# PWR_PROT.net
KiCad netlist of a schematic drawn in Altium Designer
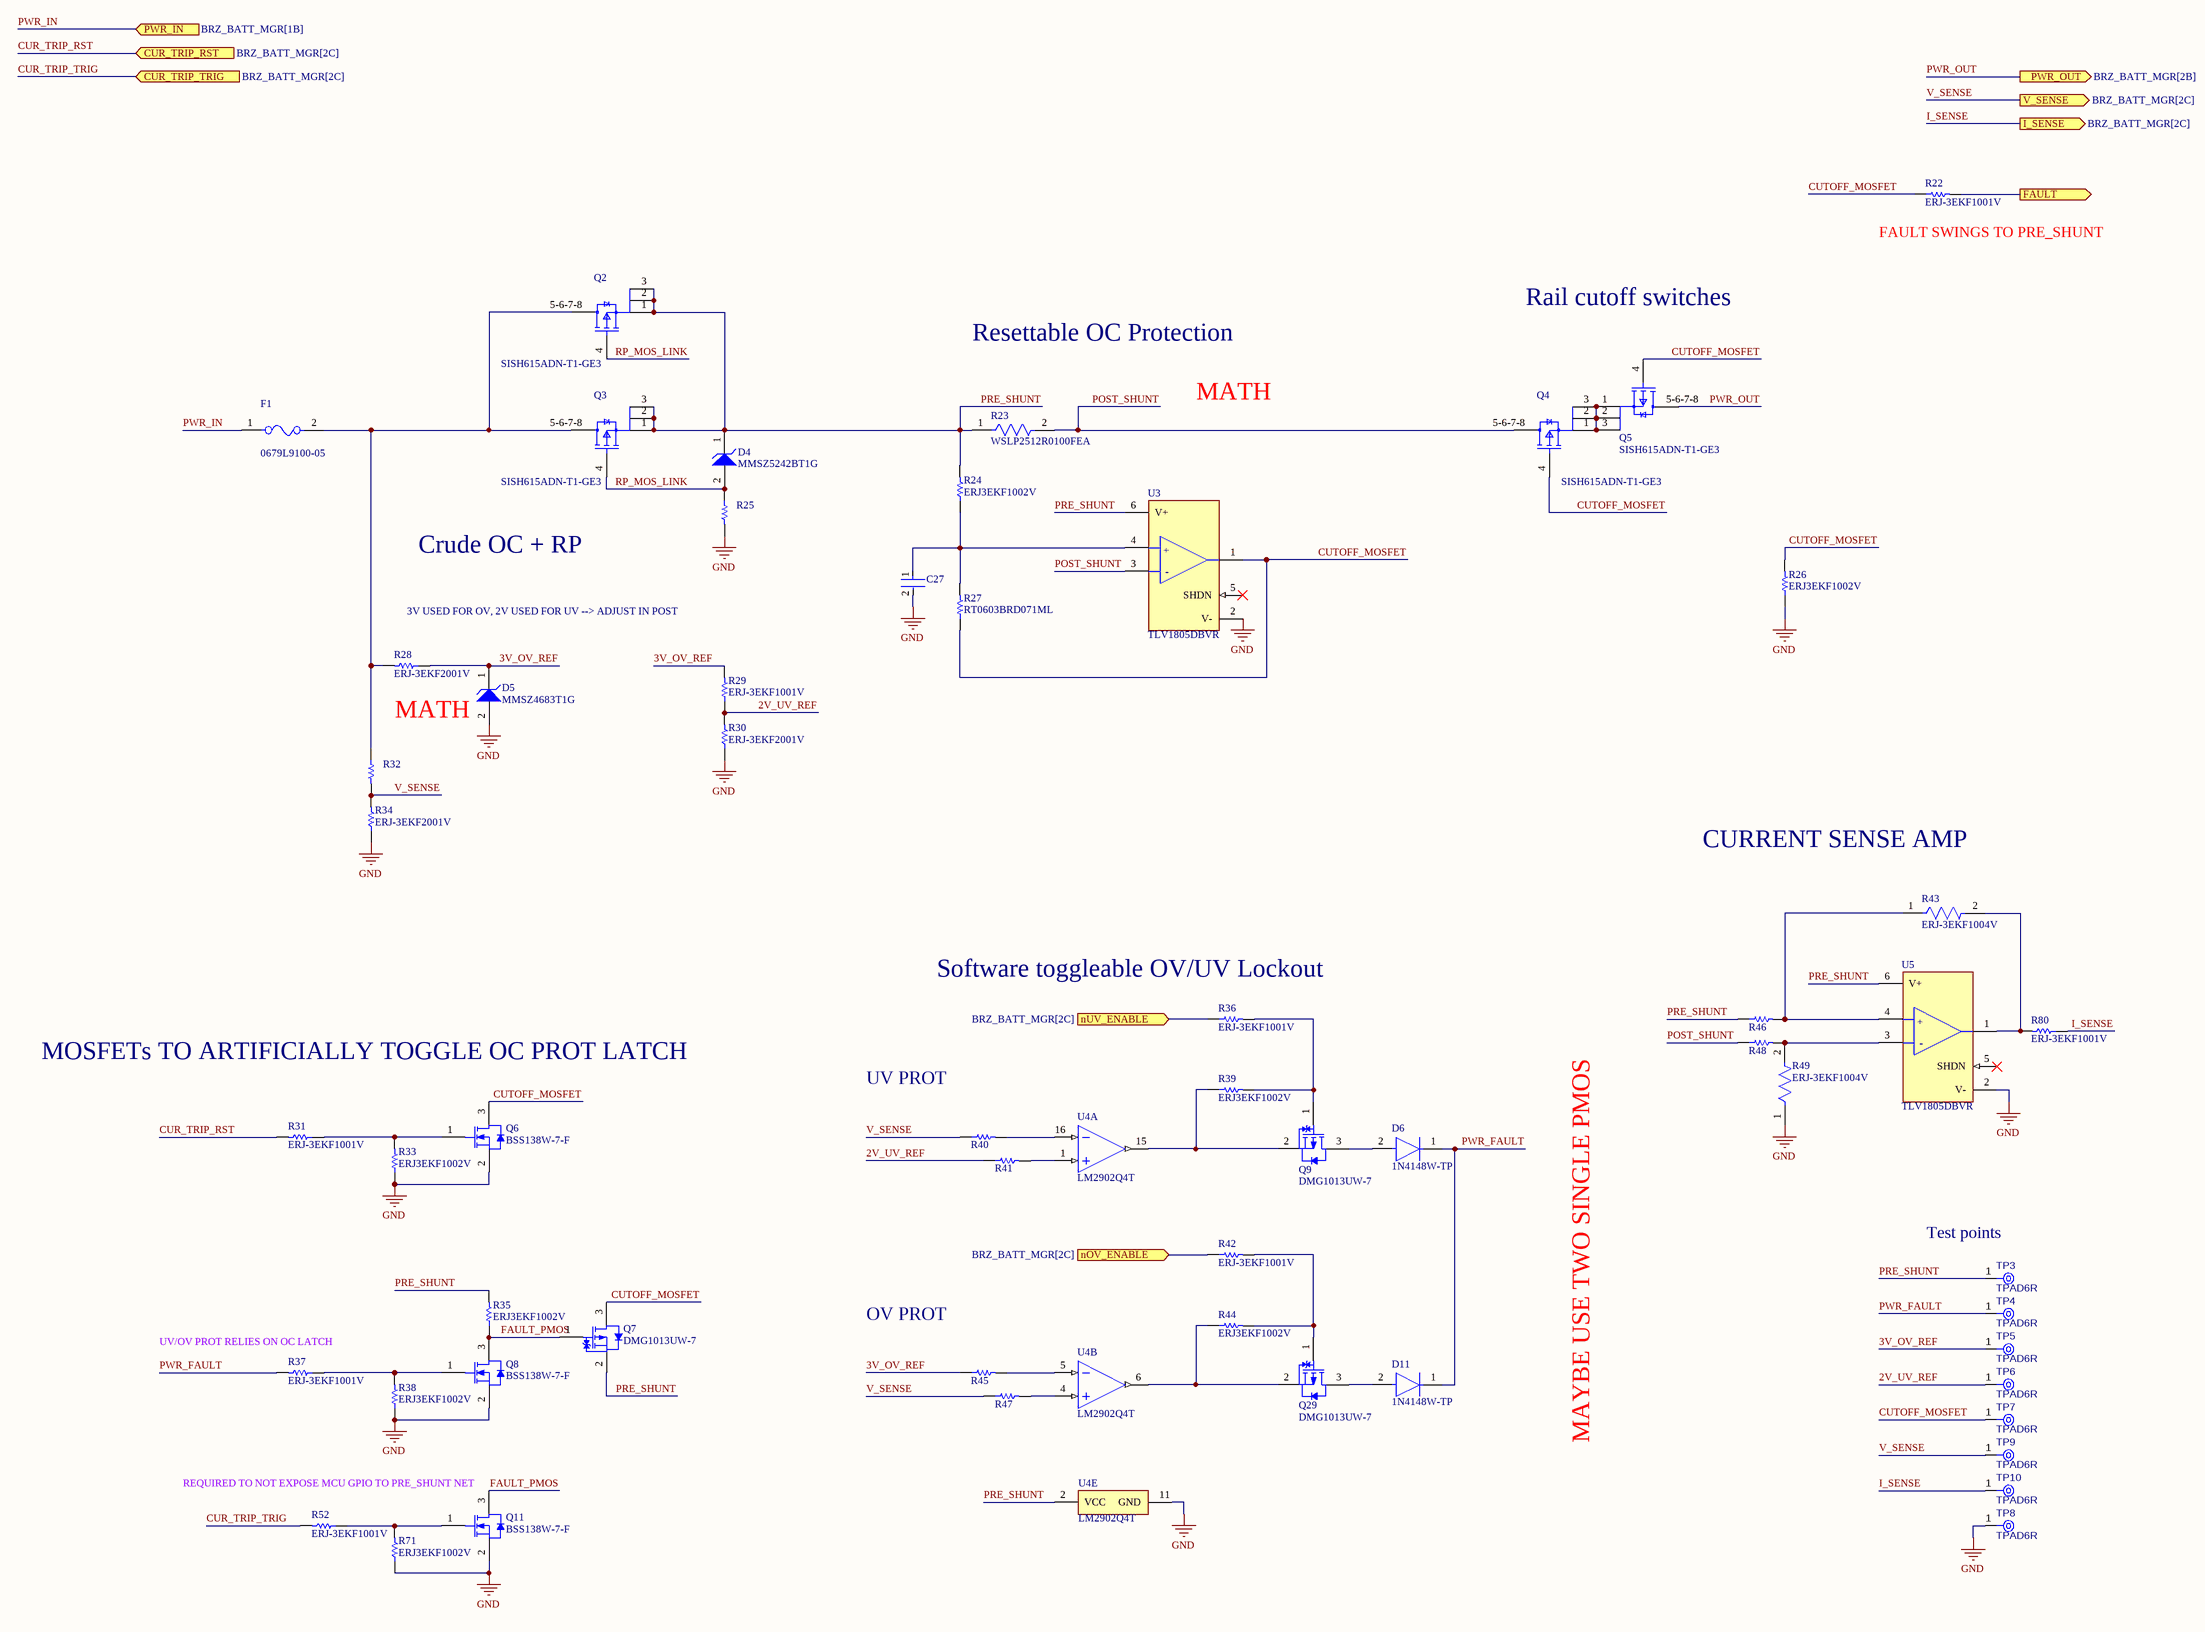
[diagram p0: PWR_PROT.SchDoc]

(export (version "E")
  (design (tool "Eeschema 10.0.6"))
  (components
    (comp (ref "C27")
      (value "GRM188R71H104KA93D")
      (footprint "FP-0402-L_1_0_0_05-W_0_5-IPC_A")
      (description "LARGE PADS, 0402 CAP, CHANGE COMMENT TO MATCH REAL P/N")
      (libsource (lib "Space Concordia") (part "b4654b650e69147ec39a6b967a45e02"))
    )
    (comp (ref "D4")
      (value "MMSZ5242BT1G")
      (footprint "ONSC-SOD-123-2-425-04_V")
      (description "Zener Voltage Regulator, 500 mW, 2-Pin SOD-123, Pb-Free, Tape and Reel")
      (fields (field (name "MANUFACTURER") "On Semiconductor"))
      (libsource (lib "Altium Content Vault") (part "ONSC-K1A2-2"))
    )
    (comp (ref "D5")
      (value "MMSZ4683T1G")
      (footprint "ONSC-SOD-123-2-425-04_V")
      (description "Zener Voltage Regulator, 500 mW, 2-Pin SOD-123, Pb-Free, Tape and Reel")
      (fields (field (name "MANUFACTURER") "On Semiconductor"))
      (libsource (lib "Altium Content Vault") (part "ONSC-K1A2-2"))
    )
    (comp (ref "D6")
      (value "1N4148W-TP")
      (footprint "FP-SOD-123-IPC_A")
      (description "DIODE GEN PURP 100V 150MA SOD123")
      (libsource (lib "Altium Content Vault") (part "d7152d700b627762746794eb795d46e"))
    )
    (comp (ref "D11")
      (value "1N4148W-TP")
      (footprint "FP-SOD-123-IPC_A")
      (description "DIODE GEN PURP 100V 150MA SOD123")
      (libsource (lib "Altium Content Vault") (part "d7152d700b627762746794eb795d46e"))
    )
    (comp (ref "F1")
      (value "0679L9100-05")
      (footprint "FP-0679L-MFG")
      (description "DIFF P#!!!\r\n\r\nFUSE BRD MNT 10A 125VAC/VDC")
      (fields
        (field (name "OCTOPART") "https://octopart.com/0679l9150-01-bel+fuse-70850665")
        (field (name "MANUFACTURER") "Bel Fuse")
      )
      (libsource (lib "Altium Content Vault") (part "5bcf9b9f640e542cf0359d10258e979"))
    )
    (comp (ref "Q2")
      (value "SISH615ADN-T1-GE3")
      (footprint "SISH615ADN-T1-GE3-Footprint-1")
      (description "Trans MOSFET P-CH 20V 22.1A 8-Pin PowerPAK 1212 EP T/R")
      (libsource (lib "uORocketry Hardware") (part "SISH615ADN-T1-GE3-Symbol-1"))
    )
    (comp (ref "Q3")
      (value "SISH615ADN-T1-GE3")
      (footprint "SISH615ADN-T1-GE3-Footprint-1")
      (description "Trans MOSFET P-CH 20V 22.1A 8-Pin PowerPAK 1212 EP T/R")
      (libsource (lib "uORocketry Hardware") (part "SISH615ADN-T1-GE3-Symbol-1"))
    )
    (comp (ref "Q4")
      (value "SISH615ADN-T1-GE3")
      (footprint "SISH615ADN-T1-GE3-Footprint-1")
      (description "Trans MOSFET P-CH 20V 22.1A 8-Pin PowerPAK 1212 EP T/R")
      (libsource (lib "uORocketry Hardware") (part "SISH615ADN-T1-GE3-Symbol-1"))
    )
    (comp (ref "Q5")
      (value "SISH615ADN-T1-GE3")
      (footprint "SISH615ADN-T1-GE3-Footprint-1")
      (description "Trans MOSFET P-CH 20V 22.1A 8-Pin PowerPAK 1212 EP T/R")
      (libsource (lib "uORocketry Hardware") (part "SISH615ADN-T1-GE3-Symbol-1"))
    )
    (comp (ref "Q6")
      (value "BSS138W-7-F")
      (footprint "DIOD-SOT323-3_V")
      (fields (field (name "MANUFACTURER") "DiodesIncorporated"))
      (libsource (lib "Altium Content Vault") (part "NEMOS-GSD-3"))
    )
    (comp (ref "Q7")
      (value "DMG1013UW-7")
      (footprint "DIOD-SOT323-3_V")
      (fields (field (name "MANUFACTURER") "Diodes Inc"))
      (libsource (lib "Altium Content Vault") (part "PEMOS-GSD-3_C"))
    )
    (comp (ref "Q8")
      (value "BSS138W-7-F")
      (footprint "DIOD-SOT323-3_V")
      (fields (field (name "MANUFACTURER") "DiodesIncorporated"))
      (libsource (lib "Altium Content Vault") (part "NEMOS-GSD-3"))
    )
    (comp (ref "Q9")
      (value "DMG1013UW-7")
      (footprint "DIOD-SOT323-3_V")
      (fields (field (name "MANUFACTURER") "Diodes Inc"))
      (libsource (lib "Altium Content Vault") (part "PEMOS-GSD-3_C"))
    )
    (comp (ref "Q11")
      (value "BSS138W-7-F")
      (footprint "DIOD-SOT323-3_V")
      (fields (field (name "MANUFACTURER") "DiodesIncorporated"))
      (libsource (lib "Altium Content Vault") (part "NEMOS-GSD-3"))
    )
    (comp (ref "Q29")
      (value "DMG1013UW-7")
      (footprint "DIOD-SOT323-3_V")
      (fields (field (name "MANUFACTURER") "Diodes Inc"))
      (libsource (lib "Altium Content Vault") (part "PEMOS-GSD-3_C"))
    )
    (comp (ref "R22")
      (value "ERJ-3EKF1001V")
      (footprint "RESC1608X55X30LL15T15")
      (fields (field (name "MANUFACTURER") "Panasonic"))
      (libsource (lib "Altium Content Vault") (part "RES"))
    )
    (comp (ref "R23")
      (value "WSLP2512R0100FEA")
      (footprint "FP-WSLP2512R0100FEA-MFG")
      (description "RES 0.01 OHM 1% 3W 2512")
      (fields (field (name "TOLERANCE") "1%"))
      (libsource (lib "Altium Content Vault") (part "1029c3af85768c4190bb7ad29bc67b5"))
    )
    (comp (ref "R24")
      (value "ERJ3EKF1002V")
      (footprint "RESC1609X55X30LL15T15")
      (description "Chip Resistor, 10 KOhm, +/- 1%, 0.1 W, -55 to 155 degC, 0603 (1608 Metric), RoHS, Tape and Reel")
      (fields (field (name "TOLERANCE") "1%") (field (name "MANUFACTURER") "Panasonic"))
      (libsource (lib "Altium Content Vault") (part "RES-2"))
    )
    (comp (ref "R25")
      (value "ERJ3EKF1002V")
      (footprint "RESC1609X55X30LL15T15")
      (description "Chip Resistor, 10 KOhm, +/- 1%, 0.1 W, -55 to 155 degC, 0603 (1608 Metric), RoHS, Tape and Reel")
      (fields (field (name "TOLERANCE") "1%") (field (name "MANUFACTURER") "Panasonic"))
      (libsource (lib "Altium Content Vault") (part "RES-2"))
    )
    (comp (ref "R26")
      (value "ERJ3EKF1002V")
      (footprint "RESC1609X55X30LL15T15")
      (description "Chip Resistor, 10 KOhm, +/- 1%, 0.1 W, -55 to 155 degC, 0603 (1608 Metric), RoHS, Tape and Reel")
      (fields (field (name "TOLERANCE") "1%") (field (name "MANUFACTURER") "Panasonic"))
      (libsource (lib "Altium Content Vault") (part "RES-2"))
    )
    (comp (ref "R27")
      (value "RT0603BRD071ML")
      (footprint "RESC1608X55X30NL20T20")
      (fields (field (name "MANUFACTURER") "Panasonic") (field (name "PART NUMBER") "ERA-3AEB163V"))
      (libsource (lib "Altium Content Vault") (part "RES"))
    )
    (comp (ref "R28")
      (value "ERJ-3EKF2001V")
      (footprint "RESC1608X55X30ML15T15")
      (fields (field (name "MANUFACTURER") "Panasonic"))
      (libsource (lib "Altium Content Vault") (part "RES"))
    )
    (comp (ref "R29")
      (value "ERJ-3EKF1001V")
      (footprint "RESC1608X55X30LL15T15")
      (fields (field (name "MANUFACTURER") "Panasonic"))
      (libsource (lib "Altium Content Vault") (part "RES"))
    )
    (comp (ref "R30")
      (value "ERJ-3EKF2001V")
      (footprint "RESC1608X55X30ML15T15")
      (fields (field (name "MANUFACTURER") "Panasonic"))
      (libsource (lib "Altium Content Vault") (part "RES"))
    )
    (comp (ref "R31")
      (value "ERJ-3EKF1001V")
      (footprint "RESC1608X55X30LL15T15")
      (fields (field (name "MANUFACTURER") "Panasonic"))
      (libsource (lib "Altium Content Vault") (part "RES"))
    )
    (comp (ref "R32")
      (value "ERJ3EKF1002V")
      (footprint "RESC1609X55X30LL15T15")
      (description "Chip Resistor, 10 KOhm, +/- 1%, 0.1 W, -55 to 155 degC, 0603 (1608 Metric), RoHS, Tape and Reel")
      (fields (field (name "TOLERANCE") "1%") (field (name "MANUFACTURER") "Panasonic"))
      (libsource (lib "Altium Content Vault") (part "RES-2"))
    )
    (comp (ref "R33")
      (value "ERJ3EKF1002V")
      (footprint "RESC1609X55X30LL15T15")
      (description "Chip Resistor, 10 KOhm, +/- 1%, 0.1 W, -55 to 155 degC, 0603 (1608 Metric), RoHS, Tape and Reel")
      (fields (field (name "TOLERANCE") "1%") (field (name "MANUFACTURER") "Panasonic"))
      (libsource (lib "Altium Content Vault") (part "RES-2"))
    )
    (comp (ref "R34")
      (value "ERJ-3EKF2001V")
      (footprint "RESC1608X55X30ML15T15")
      (fields (field (name "MANUFACTURER") "Panasonic"))
      (libsource (lib "Altium Content Vault") (part "RES"))
    )
    (comp (ref "R35")
      (value "ERJ3EKF1002V")
      (footprint "RESC1609X55X30LL15T15")
      (description "Chip Resistor, 10 KOhm, +/- 1%, 0.1 W, -55 to 155 degC, 0603 (1608 Metric), RoHS, Tape and Reel")
      (fields (field (name "TOLERANCE") "1%") (field (name "MANUFACTURER") "Panasonic"))
      (libsource (lib "Altium Content Vault") (part "RES-2"))
    )
    (comp (ref "R36")
      (value "ERJ-3EKF1001V")
      (footprint "RESC1608X55X30LL15T15")
      (fields (field (name "MANUFACTURER") "Panasonic"))
      (libsource (lib "Altium Content Vault") (part "RES"))
    )
    (comp (ref "R37")
      (value "ERJ-3EKF1001V")
      (footprint "RESC1608X55X30LL15T15")
      (fields (field (name "MANUFACTURER") "Panasonic"))
      (libsource (lib "Altium Content Vault") (part "RES"))
    )
    (comp (ref "R38")
      (value "ERJ3EKF1002V")
      (footprint "RESC1609X55X30LL15T15")
      (description "Chip Resistor, 10 KOhm, +/- 1%, 0.1 W, -55 to 155 degC, 0603 (1608 Metric), RoHS, Tape and Reel")
      (fields (field (name "TOLERANCE") "1%") (field (name "MANUFACTURER") "Panasonic"))
      (libsource (lib "Altium Content Vault") (part "RES-2"))
    )
    (comp (ref "R39")
      (value "ERJ3EKF1002V")
      (footprint "RESC1609X55X30LL15T15")
      (description "Chip Resistor, 10 KOhm, +/- 1%, 0.1 W, -55 to 155 degC, 0603 (1608 Metric), RoHS, Tape and Reel")
      (fields (field (name "TOLERANCE") "1%") (field (name "MANUFACTURER") "Panasonic"))
      (libsource (lib "Altium Content Vault") (part "RES-2"))
    )
    (comp (ref "R40")
      (value "ERJ3EKF1002V")
      (footprint "RESC1609X55X30LL15T15")
      (description "Chip Resistor, 10 KOhm, +/- 1%, 0.1 W, -55 to 155 degC, 0603 (1608 Metric), RoHS, Tape and Reel")
      (fields (field (name "TOLERANCE") "1%") (field (name "MANUFACTURER") "Panasonic"))
      (libsource (lib "Altium Content Vault") (part "RES-2"))
    )
    (comp (ref "R41")
      (value "ERJ3EKF1002V")
      (footprint "RESC1609X55X30LL15T15")
      (description "Chip Resistor, 10 KOhm, +/- 1%, 0.1 W, -55 to 155 degC, 0603 (1608 Metric), RoHS, Tape and Reel")
      (fields (field (name "TOLERANCE") "1%") (field (name "MANUFACTURER") "Panasonic"))
      (libsource (lib "Altium Content Vault") (part "RES-2"))
    )
    (comp (ref "R42")
      (value "ERJ-3EKF1001V")
      (footprint "RESC1608X55X30LL15T15")
      (fields (field (name "MANUFACTURER") "Panasonic"))
      (libsource (lib "Altium Content Vault") (part "RES"))
    )
    (comp (ref "R43")
      (value "ERJ-3EKF1004V")
      (footprint "FP-ERJ3EK-IPC_C")
      (description "RES SMD 1M OHM 1% 1/10W 0603")
      (fields (field (name "TOLERANCE") "1%"))
      (libsource (lib "Altium Content Vault") (part "1029c3af85768c4190bb7ad29bc67b5"))
    )
    (comp (ref "R44")
      (value "ERJ3EKF1002V")
      (footprint "RESC1609X55X30LL15T15")
      (description "Chip Resistor, 10 KOhm, +/- 1%, 0.1 W, -55 to 155 degC, 0603 (1608 Metric), RoHS, Tape and Reel")
      (fields (field (name "TOLERANCE") "1%") (field (name "MANUFACTURER") "Panasonic"))
      (libsource (lib "Altium Content Vault") (part "RES-2"))
    )
    (comp (ref "R45")
      (value "ERJ3EKF1002V")
      (footprint "RESC1609X55X30LL15T15")
      (description "Chip Resistor, 10 KOhm, +/- 1%, 0.1 W, -55 to 155 degC, 0603 (1608 Metric), RoHS, Tape and Reel")
      (fields (field (name "TOLERANCE") "1%") (field (name "MANUFACTURER") "Panasonic"))
      (libsource (lib "Altium Content Vault") (part "RES-2"))
    )
    (comp (ref "R46")
      (value "ERJ3EKF1002V")
      (footprint "RESC1609X55X30LL15T15")
      (description "Chip Resistor, 10 KOhm, +/- 1%, 0.1 W, -55 to 155 degC, 0603 (1608 Metric), RoHS, Tape and Reel")
      (fields (field (name "TOLERANCE") "1%") (field (name "MANUFACTURER") "Panasonic"))
      (libsource (lib "Altium Content Vault") (part "RES-2"))
    )
    (comp (ref "R47")
      (value "ERJ3EKF1002V")
      (footprint "RESC1609X55X30LL15T15")
      (description "Chip Resistor, 10 KOhm, +/- 1%, 0.1 W, -55 to 155 degC, 0603 (1608 Metric), RoHS, Tape and Reel")
      (fields (field (name "TOLERANCE") "1%") (field (name "MANUFACTURER") "Panasonic"))
      (libsource (lib "Altium Content Vault") (part "RES-2"))
    )
    (comp (ref "R48")
      (value "ERJ3EKF1002V")
      (footprint "RESC1609X55X30LL15T15")
      (description "Chip Resistor, 10 KOhm, +/- 1%, 0.1 W, -55 to 155 degC, 0603 (1608 Metric), RoHS, Tape and Reel")
      (fields (field (name "TOLERANCE") "1%") (field (name "MANUFACTURER") "Panasonic"))
      (libsource (lib "Altium Content Vault") (part "RES-2"))
    )
    (comp (ref "R49")
      (value "ERJ-3EKF1004V")
      (footprint "FP-ERJ3EK-IPC_C")
      (description "RES SMD 1M OHM 1% 1/10W 0603")
      (fields (field (name "TOLERANCE") "1%"))
      (libsource (lib "Altium Content Vault") (part "1029c3af85768c4190bb7ad29bc67b5"))
    )
    (comp (ref "R52")
      (value "ERJ-3EKF1001V")
      (footprint "RESC1608X55X30LL15T15")
      (fields (field (name "MANUFACTURER") "Panasonic"))
      (libsource (lib "Altium Content Vault") (part "RES"))
    )
    (comp (ref "R71")
      (value "ERJ3EKF1002V")
      (footprint "RESC1609X55X30LL15T15")
      (description "Chip Resistor, 10 KOhm, +/- 1%, 0.1 W, -55 to 155 degC, 0603 (1608 Metric), RoHS, Tape and Reel")
      (fields (field (name "TOLERANCE") "1%") (field (name "MANUFACTURER") "Panasonic"))
      (libsource (lib "Altium Content Vault") (part "RES-2"))
    )
    (comp (ref "R80")
      (value "ERJ-3EKF1001V")
      (footprint "RESC1608X55X30LL15T15")
      (fields (field (name "MANUFACTURER") "Panasonic"))
      (libsource (lib "Altium Content Vault") (part "RES"))
    )
    (comp (ref "TP3")
      (value "TPAD6R")
      (footprint "TP06R")
      (description "0.6mm round")
      (libsource (lib "uORocketry Hardware") (part "CMP-001-0001-4"))
    )
    (comp (ref "TP4")
      (value "TPAD6R")
      (footprint "TP06R")
      (description "0.6mm round")
      (libsource (lib "uORocketry Hardware") (part "CMP-001-0001-4"))
    )
    (comp (ref "TP5")
      (value "TPAD6R")
      (footprint "TP06R")
      (description "0.6mm round")
      (libsource (lib "uORocketry Hardware") (part "CMP-001-0001-4"))
    )
    (comp (ref "TP6")
      (value "TPAD6R")
      (footprint "TP06R")
      (description "0.6mm round")
      (libsource (lib "uORocketry Hardware") (part "CMP-001-0001-4"))
    )
    (comp (ref "TP7")
      (value "TPAD6R")
      (footprint "TP06R")
      (description "0.6mm round")
      (libsource (lib "uORocketry Hardware") (part "CMP-001-0001-4"))
    )
    (comp (ref "TP8")
      (value "TPAD6R")
      (footprint "TP06R")
      (description "0.6mm round")
      (libsource (lib "uORocketry Hardware") (part "CMP-001-0001-4"))
    )
    (comp (ref "TP9")
      (value "TPAD6R")
      (footprint "TP06R")
      (description "0.6mm round")
      (libsource (lib "uORocketry Hardware") (part "CMP-001-0001-4"))
    )
    (comp (ref "TP10")
      (value "TPAD6R")
      (footprint "TP06R")
      (description "0.6mm round")
      (libsource (lib "uORocketry Hardware") (part "CMP-001-0001-4"))
    )
    (comp (ref "U3")
      (value "TLV1805DBVR")
      (footprint "FP-DBV0006A-IPC_C")
      (description "40V, RAIL-TO-RAIL INPUT, PUSH-PU")
      (libsource (lib "Altium Content Vault") (part "c7aa3bc3dbf0dc8b0b0354779bd1228"))
    )
    (comp (ref "U4")
      (value "LM2902Q4T")
      (footprint "LM2902Q4T-Footprint-1")
      (description "LM2902 Series 30 V 1.3 MHz Low-Power Quad Operational Amplifier - QFN-16 (3x3)")
      (libsource (lib "uORocketry Hardware") (part "LM2902Q4T"))
    )
    (comp (ref "U5")
      (value "TLV1805DBVR")
      (footprint "FP-DBV0006A-IPC_C")
      (description "40V, RAIL-TO-RAIL INPUT, PUSH-PU")
      (libsource (lib "Altium Content Vault") (part "c7aa3bc3dbf0dc8b0b0354779bd1228"))
    )
  )
  (nets
    (net (code "1") (name "/2V_UV_REF") (class "Default")
      (node (ref "R29") (pin "1") (pinfunction "1_1") (pintype "passive"))
      (node (ref "R30") (pin "2") (pinfunction "2_2") (pintype "passive"))
      (node (ref "R41") (pin "1") (pinfunction "1_1") (pintype "passive"))
      (node (ref "TP6") (pin "1") (pinfunction "TP_1") (pintype "passive"))
    )
    (net (code "2") (name "/3V_OV_REF") (class "Default")
      (node (ref "D5") (pin "1") (pinfunction "K_1") (pintype "passive"))
      (node (ref "R28") (pin "1") (pinfunction "1_1") (pintype "passive"))
      (node (ref "R29") (pin "2") (pinfunction "2_2") (pintype "passive"))
      (node (ref "R45") (pin "1") (pinfunction "1_1") (pintype "passive"))
      (node (ref "TP5") (pin "1") (pinfunction "TP_1") (pintype "passive"))
    )
    (net (code "3") (name "/CUR_TRIP_RST") (class "Default")
      (node (ref "R31") (pin "2") (pinfunction "2_2") (pintype "passive"))
    )
    (net (code "4") (name "/CUR_TRIP_TRIG") (class "Default")
      (node (ref "R52") (pin "2") (pinfunction "2_2") (pintype "passive"))
    )
    (net (code "5") (name "/CUTOFF_MOSFET") (class "Default")
      (node (ref "Q4") (pin "4") (pinfunction "G_4") (pintype "passive"))
      (node (ref "Q5") (pin "4") (pinfunction "G_4") (pintype "passive"))
      (node (ref "Q6") (pin "3") (pinfunction "D_3") (pintype "passive"))
      (node (ref "Q7") (pin "3") (pinfunction "D_3") (pintype "passive"))
      (node (ref "R22") (pin "1") (pinfunction "1_1") (pintype "passive"))
      (node (ref "R26") (pin "2") (pinfunction "2_2") (pintype "passive"))
      (node (ref "R27") (pin "1") (pinfunction "1_1") (pintype "passive"))
      (node (ref "TP7") (pin "1") (pinfunction "TP_1") (pintype "passive"))
      (node (ref "U3") (pin "1") (pinfunction "OUT_1") (pintype "passive"))
    )
    (net (code "6") (name "/FAULT") (class "Default")
      (node (ref "R22") (pin "2") (pinfunction "2_2") (pintype "passive"))
    )
    (net (code "7") (name "/FAULT_PMOS") (class "Default")
      (node (ref "Q11") (pin "3") (pinfunction "D_3") (pintype "passive"))
      (node (ref "Q7") (pin "1") (pinfunction "G_1") (pintype "passive"))
      (node (ref "Q8") (pin "3") (pinfunction "D_3") (pintype "passive"))
      (node (ref "R35") (pin "1") (pinfunction "1_1") (pintype "passive"))
    )
    (net (code "8") (name "/I_SENSE") (class "Default")
      (node (ref "R80") (pin "1") (pinfunction "1_1") (pintype "passive"))
      (node (ref "TP10") (pin "1") (pinfunction "TP_1") (pintype "passive"))
    )
    (net (code "9") (name "/POST_SHUNT") (class "Default")
      (node (ref "Q4") (pin "5-6-7-8") (pinfunction "D_5-6-7-8") (pintype "passive"))
      (node (ref "R23") (pin "2") (pinfunction "2_2") (pintype "passive"))
      (node (ref "R48") (pin "1") (pinfunction "1_1") (pintype "passive"))
      (node (ref "U3") (pin "3") (pinfunction "-IN_3") (pintype "tri_state"))
    )
    (net (code "10") (name "/PRE_SHUNT") (class "Default")
      (node (ref "D4") (pin "1") (pinfunction "K_1") (pintype "passive"))
      (node (ref "Q2") (pin "1") (pinfunction "S_1") (pintype "passive"))
      (node (ref "Q2") (pin "2") (pinfunction "S_2") (pintype "passive"))
      (node (ref "Q2") (pin "3") (pinfunction "S_3") (pintype "passive"))
      (node (ref "Q3") (pin "1") (pinfunction "S_1") (pintype "passive"))
      (node (ref "Q3") (pin "2") (pinfunction "S_2") (pintype "passive"))
      (node (ref "Q3") (pin "3") (pinfunction "S_3") (pintype "passive"))
      (node (ref "Q7") (pin "2") (pinfunction "S_2") (pintype "passive"))
      (node (ref "R23") (pin "1") (pinfunction "1_1") (pintype "passive"))
      (node (ref "R24") (pin "2") (pinfunction "2_2") (pintype "passive"))
      (node (ref "R35") (pin "2") (pinfunction "2_2") (pintype "passive"))
      (node (ref "R46") (pin "1") (pinfunction "1_1") (pintype "passive"))
      (node (ref "TP3") (pin "1") (pinfunction "TP_1") (pintype "passive"))
      (node (ref "U3") (pin "6") (pinfunction "V+_6") (pintype "power_in"))
      (node (ref "U4") (pin "2") (pinfunction "VCC_2") (pintype "power_in"))
      (node (ref "U5") (pin "6") (pinfunction "V+_6") (pintype "power_in"))
    )
    (net (code "11") (name "/PWR_FAULT") (class "Default")
      (node (ref "D11") (pin "1") (pinfunction "C_1") (pintype "passive"))
      (node (ref "D6") (pin "1") (pinfunction "C_1") (pintype "passive"))
      (node (ref "R37") (pin "2") (pinfunction "2_2") (pintype "passive"))
      (node (ref "TP4") (pin "1") (pinfunction "TP_1") (pintype "passive"))
    )
    (net (code "12") (name "/PWR_IN") (class "Default")
      (node (ref "F1") (pin "1") (pinfunction "1_1") (pintype "passive"))
    )
    (net (code "13") (name "/PWR_OUT") (class "Default")
      (node (ref "Q5") (pin "5-6-7-8") (pinfunction "D_5-6-7-8") (pintype "passive"))
    )
    (net (code "14") (name "/RP_MOS_LINK") (class "Default")
      (node (ref "D4") (pin "2") (pinfunction "A_2") (pintype "passive"))
      (node (ref "Q2") (pin "4") (pinfunction "G_4") (pintype "passive"))
      (node (ref "Q3") (pin "4") (pinfunction "G_4") (pintype "passive"))
      (node (ref "R25") (pin "1") (pinfunction "1_1") (pintype "passive"))
    )
    (net (code "15") (name "/V_SENSE") (class "Default")
      (node (ref "R32") (pin "2") (pinfunction "2_2") (pintype "passive"))
      (node (ref "R34") (pin "2") (pinfunction "2_2") (pintype "passive"))
      (node (ref "R40") (pin "1") (pinfunction "1_1") (pintype "passive"))
      (node (ref "R47") (pin "1") (pinfunction "1_1") (pintype "passive"))
      (node (ref "TP9") (pin "1") (pinfunction "TP_1") (pintype "passive"))
    )
    (net (code "16") (name "/nOV_ENABLE") (class "Default")
      (node (ref "R42") (pin "1") (pinfunction "1_1") (pintype "passive"))
    )
    (net (code "17") (name "/nUV_ENABLE") (class "Default")
      (node (ref "R36") (pin "1") (pinfunction "1_1") (pintype "passive"))
    )
    (net (code "18") (name "GND") (class "Default")
      (node (ref "C27") (pin "2") (pinfunction "2_2") (pintype "passive"))
      (node (ref "D5") (pin "2") (pinfunction "A_2") (pintype "passive"))
      (node (ref "Q11") (pin "2") (pinfunction "S_2") (pintype "passive"))
      (node (ref "Q6") (pin "2") (pinfunction "S_2") (pintype "passive"))
      (node (ref "Q8") (pin "2") (pinfunction "S_2") (pintype "passive"))
      (node (ref "R25") (pin "2") (pinfunction "2_2") (pintype "passive"))
      (node (ref "R26") (pin "1") (pinfunction "1_1") (pintype "passive"))
      (node (ref "R30") (pin "1") (pinfunction "1_1") (pintype "passive"))
      (node (ref "R33") (pin "1") (pinfunction "1_1") (pintype "passive"))
      (node (ref "R34") (pin "1") (pinfunction "1_1") (pintype "passive"))
      (node (ref "R38") (pin "1") (pinfunction "1_1") (pintype "passive"))
      (node (ref "R49") (pin "1") (pinfunction "1_1") (pintype "passive"))
      (node (ref "R71") (pin "1") (pinfunction "1_1") (pintype "passive"))
      (node (ref "TP8") (pin "1") (pinfunction "TP_1") (pintype "passive"))
      (node (ref "U3") (pin "2") (pinfunction "V-_2") (pintype "power_in"))
      (node (ref "U4") (pin "11") (pinfunction "GND_11") (pintype "power_in"))
      (node (ref "U5") (pin "2") (pinfunction "V-_2") (pintype "power_in"))
    )
    (net (code "19") (name "Net-(D6-A)") (class "Default")
      (node (ref "D6") (pin "2") (pinfunction "A_2") (pintype "passive"))
      (node (ref "Q9") (pin "3") (pinfunction "D_3") (pintype "passive"))
    )
    (net (code "20") (name "Net-(D11-A)") (class "Default")
      (node (ref "D11") (pin "2") (pinfunction "A_2") (pintype "passive"))
      (node (ref "Q29") (pin "3") (pinfunction "D_3") (pintype "passive"))
    )
    (net (code "21") (name "Net-(Q2-D)") (class "Default")
      (node (ref "F1") (pin "2") (pinfunction "2_2") (pintype "passive"))
      (node (ref "Q2") (pin "5-6-7-8") (pinfunction "D_5-6-7-8") (pintype "passive"))
      (node (ref "Q3") (pin "5-6-7-8") (pinfunction "D_5-6-7-8") (pintype "passive"))
      (node (ref "R28") (pin "2") (pinfunction "2_2") (pintype "passive"))
      (node (ref "R32") (pin "1") (pinfunction "1_1") (pintype "passive"))
    )
    (net (code "22") (name "Net-(Q4-S-Pad1)") (class "Default")
      (node (ref "Q4") (pin "1") (pinfunction "S_1") (pintype "passive"))
      (node (ref "Q4") (pin "2") (pinfunction "S_2") (pintype "passive"))
      (node (ref "Q4") (pin "3") (pinfunction "S_3") (pintype "passive"))
      (node (ref "Q5") (pin "1") (pinfunction "S_1") (pintype "passive"))
      (node (ref "Q5") (pin "2") (pinfunction "S_2") (pintype "passive"))
      (node (ref "Q5") (pin "3") (pinfunction "S_3") (pintype "passive"))
    )
    (net (code "23") (name "Net-(Q6-G)") (class "Default")
      (node (ref "Q6") (pin "1") (pinfunction "G_1") (pintype "passive"))
      (node (ref "R31") (pin "1") (pinfunction "1_1") (pintype "passive"))
      (node (ref "R33") (pin "2") (pinfunction "2_2") (pintype "passive"))
    )
    (net (code "24") (name "Net-(Q8-G)") (class "Default")
      (node (ref "Q8") (pin "1") (pinfunction "G_1") (pintype "passive"))
      (node (ref "R37") (pin "1") (pinfunction "1_1") (pintype "passive"))
      (node (ref "R38") (pin "2") (pinfunction "2_2") (pintype "passive"))
    )
    (net (code "25") (name "Net-(Q9-G)") (class "Default")
      (node (ref "Q9") (pin "1") (pinfunction "G_1") (pintype "passive"))
      (node (ref "R36") (pin "2") (pinfunction "2_2") (pintype "passive"))
      (node (ref "R39") (pin "2") (pinfunction "2_2") (pintype "passive"))
    )
    (net (code "26") (name "Net-(Q9-S)") (class "Default")
      (node (ref "Q9") (pin "2") (pinfunction "S_2") (pintype "passive"))
      (node (ref "R39") (pin "1") (pinfunction "1_1") (pintype "passive"))
      (node (ref "U4") (pin "15") (pinfunction "1OUT_15") (pintype "output"))
    )
    (net (code "27") (name "Net-(Q11-G)") (class "Default")
      (node (ref "Q11") (pin "1") (pinfunction "G_1") (pintype "passive"))
      (node (ref "R52") (pin "1") (pinfunction "1_1") (pintype "passive"))
      (node (ref "R71") (pin "2") (pinfunction "2_2") (pintype "passive"))
    )
    (net (code "28") (name "Net-(Q29-G)") (class "Default")
      (node (ref "Q29") (pin "1") (pinfunction "G_1") (pintype "passive"))
      (node (ref "R42") (pin "2") (pinfunction "2_2") (pintype "passive"))
      (node (ref "R44") (pin "2") (pinfunction "2_2") (pintype "passive"))
    )
    (net (code "29") (name "Net-(Q29-S)") (class "Default")
      (node (ref "Q29") (pin "2") (pinfunction "S_2") (pintype "passive"))
      (node (ref "R44") (pin "1") (pinfunction "1_1") (pintype "passive"))
      (node (ref "U4") (pin "6") (pinfunction "2OUT_6") (pintype "output"))
    )
    (net (code "30") (name "Net-(U3-+IN)") (class "Default")
      (node (ref "C27") (pin "1") (pinfunction "1_1") (pintype "passive"))
      (node (ref "R24") (pin "1") (pinfunction "1_1") (pintype "passive"))
      (node (ref "R27") (pin "2") (pinfunction "2_2") (pintype "passive"))
      (node (ref "U3") (pin "4") (pinfunction "+IN_4") (pintype "tri_state"))
    )
    (net (code "31") (name "Net-(U4A-1IN+)") (class "Default")
      (node (ref "R41") (pin "2") (pinfunction "2_2") (pintype "passive"))
      (node (ref "U4") (pin "1") (pinfunction "1IN+_1") (pintype "input"))
    )
    (net (code "32") (name "Net-(U4A-1IN-)") (class "Default")
      (node (ref "R40") (pin "2") (pinfunction "2_2") (pintype "passive"))
      (node (ref "U4") (pin "16") (pinfunction "1IN-_16") (pintype "input"))
    )
    (net (code "33") (name "Net-(U4B-2IN+)") (class "Default")
      (node (ref "R47") (pin "2") (pinfunction "2_2") (pintype "passive"))
      (node (ref "U4") (pin "4") (pinfunction "2IN+_4") (pintype "input"))
    )
    (net (code "34") (name "Net-(U4B-2IN-)") (class "Default")
      (node (ref "R45") (pin "2") (pinfunction "2_2") (pintype "passive"))
      (node (ref "U4") (pin "5") (pinfunction "2IN-_5") (pintype "input"))
    )
    (net (code "35") (name "Net-(U5-+IN)") (class "Default")
      (node (ref "R43") (pin "1") (pinfunction "1_1") (pintype "passive"))
      (node (ref "R46") (pin "2") (pinfunction "2_2") (pintype "passive"))
      (node (ref "U5") (pin "4") (pinfunction "+IN_4") (pintype "tri_state"))
    )
    (net (code "36") (name "Net-(U5--IN)") (class "Default")
      (node (ref "R48") (pin "2") (pinfunction "2_2") (pintype "passive"))
      (node (ref "R49") (pin "2") (pinfunction "2_2") (pintype "passive"))
      (node (ref "U5") (pin "3") (pinfunction "-IN_3") (pintype "tri_state"))
    )
    (net (code "37") (name "Net-(U5-OUT)") (class "Default")
      (node (ref "R43") (pin "2") (pinfunction "2_2") (pintype "passive"))
      (node (ref "R80") (pin "2") (pinfunction "2_2") (pintype "passive"))
      (node (ref "U5") (pin "1") (pinfunction "OUT_1") (pintype "passive"))
    )
    (net (code "38") (name "unconnected-(U3-SHDN-Pad5)") (class "Default")
      (node (ref "U3") (pin "5") (pinfunction "SHDN_5") (pintype "input+no_connect"))
    )
    (net (code "39") (name "unconnected-(U5-SHDN-Pad5)") (class "Default")
      (node (ref "U5") (pin "5") (pinfunction "SHDN_5") (pintype "input+no_connect"))
    )
  )
)
